# rgb-board.net
KiCad netlist of a schematic drawn in EAGLE
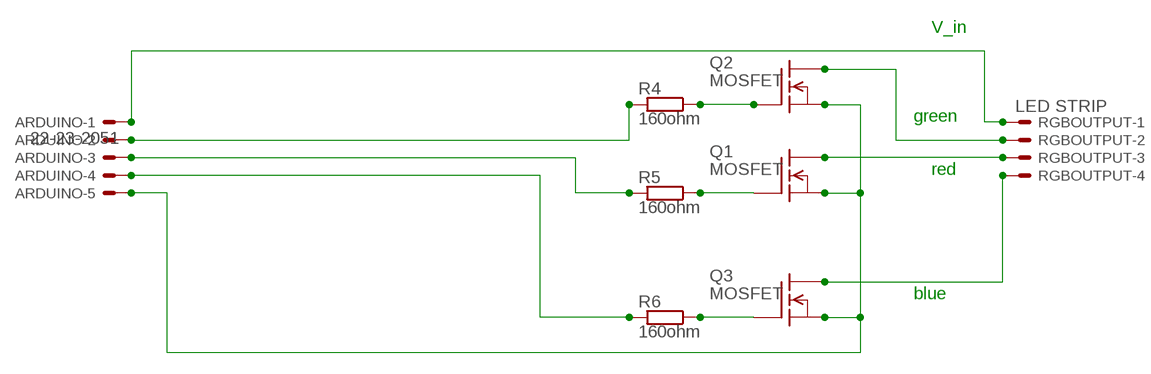
[diagram p0: schematic, sheet 1]

(export (version "E")
  (design (tool "Eeschema 10.0.6"))
  (components
    (comp (ref "ARDUINO")
      (value "22-23-2051")
      (footprint "eagle-import:22-23-2051")
      (fields (field (name "MF") "MOLEX"))
      (libsource (lib "eagle-import") (part "22-23-2051"))
    )
    (comp (ref "Q1")
      (value "MOSFET")
      (footprint "eagle-import:TO220")
      (libsource (lib "eagle-import") (part "BUZ71"))
    )
    (comp (ref "Q2")
      (value "MOSFET")
      (footprint "eagle-import:TO220")
      (libsource (lib "eagle-import") (part "BUZ71"))
    )
    (comp (ref "Q3")
      (value "MOSFET")
      (footprint "eagle-import:TO220")
      (libsource (lib "eagle-import") (part "BUZ71"))
    )
    (comp (ref "R4")
      (value "160ohm")
      (footprint "eagle-import:SMS-WAV")
      (libsource (lib "eagle-import") (part "SMR-WAV"))
    )
    (comp (ref "R5")
      (value "160ohm")
      (footprint "eagle-import:SMS-WAV")
      (libsource (lib "eagle-import") (part "SMR-WAV"))
    )
    (comp (ref "R6")
      (value "160ohm")
      (footprint "eagle-import:SMS-WAV")
      (libsource (lib "eagle-import") (part "SMR-WAV"))
    )
    (comp (ref "RGBOUTPUT")
      (value "LED STRIP")
      (footprint "eagle-import:22-23-2041")
      (fields (field (name "MF") "MOLEX") (field (name "MPN") "22-23-2041"))
      (libsource (lib "eagle-import") (part "22-23-2041"))
    )
  )
  (nets
    (net (code "1") (name "Net-(ARDUINOA-S)") (class "Default")
      (node (ref "ARDUINO") (pin "1") (pinfunction "S_1") (pintype "passive"))
      (node (ref "RGBOUTPUT") (pin "1") (pinfunction "S_1") (pintype "passive"))
    )
    (net (code "2") (name "Net-(ARDUINOB-S)") (class "Default")
      (node (ref "ARDUINO") (pin "2") (pinfunction "S_2") (pintype "passive"))
      (node (ref "R4") (pin "2") (pinfunction "2_2") (pintype "passive"))
    )
    (net (code "3") (name "Net-(ARDUINOC-S)") (class "Default")
      (node (ref "ARDUINO") (pin "3") (pinfunction "S_3") (pintype "passive"))
      (node (ref "R5") (pin "2") (pinfunction "2_2") (pintype "passive"))
    )
    (net (code "4") (name "Net-(ARDUINOD-S)") (class "Default")
      (node (ref "ARDUINO") (pin "4") (pinfunction "S_4") (pintype "passive"))
      (node (ref "R6") (pin "2") (pinfunction "2_2") (pintype "passive"))
    )
    (net (code "5") (name "Net-(ARDUINOE-S)") (class "Default")
      (node (ref "ARDUINO") (pin "5") (pinfunction "S_5") (pintype "passive"))
      (node (ref "Q1") (pin "3") (pinfunction "S_3") (pintype "passive"))
      (node (ref "Q2") (pin "3") (pinfunction "S_3") (pintype "passive"))
      (node (ref "Q3") (pin "3") (pinfunction "S_3") (pintype "passive"))
    )
    (net (code "6") (name "Net-(Q1-D)") (class "Default")
      (node (ref "Q1") (pin "2") (pinfunction "D_2") (pintype "passive"))
      (node (ref "RGBOUTPUT") (pin "3") (pinfunction "S_3") (pintype "passive"))
    )
    (net (code "7") (name "Net-(Q1-G)") (class "Default")
      (node (ref "Q1") (pin "1") (pinfunction "G_1") (pintype "passive"))
      (node (ref "R5") (pin "1") (pinfunction "1_1") (pintype "passive"))
    )
    (net (code "8") (name "Net-(Q2-D)") (class "Default")
      (node (ref "Q2") (pin "2") (pinfunction "D_2") (pintype "passive"))
      (node (ref "RGBOUTPUT") (pin "2") (pinfunction "S_2") (pintype "passive"))
    )
    (net (code "9") (name "Net-(Q2-G)") (class "Default")
      (node (ref "Q2") (pin "1") (pinfunction "G_1") (pintype "passive"))
      (node (ref "R4") (pin "1") (pinfunction "1_1") (pintype "passive"))
    )
    (net (code "10") (name "Net-(Q3-D)") (class "Default")
      (node (ref "Q3") (pin "2") (pinfunction "D_2") (pintype "passive"))
      (node (ref "RGBOUTPUT") (pin "4") (pinfunction "S_4") (pintype "passive"))
    )
    (net (code "11") (name "Net-(Q3-G)") (class "Default")
      (node (ref "Q3") (pin "1") (pinfunction "G_1") (pintype "passive"))
      (node (ref "R6") (pin "1") (pinfunction "1_1") (pintype "passive"))
    )
  )
)
